# Sheet_Course_Mitr.net
KiCad netlist of a schematic drawn in Altium Designer
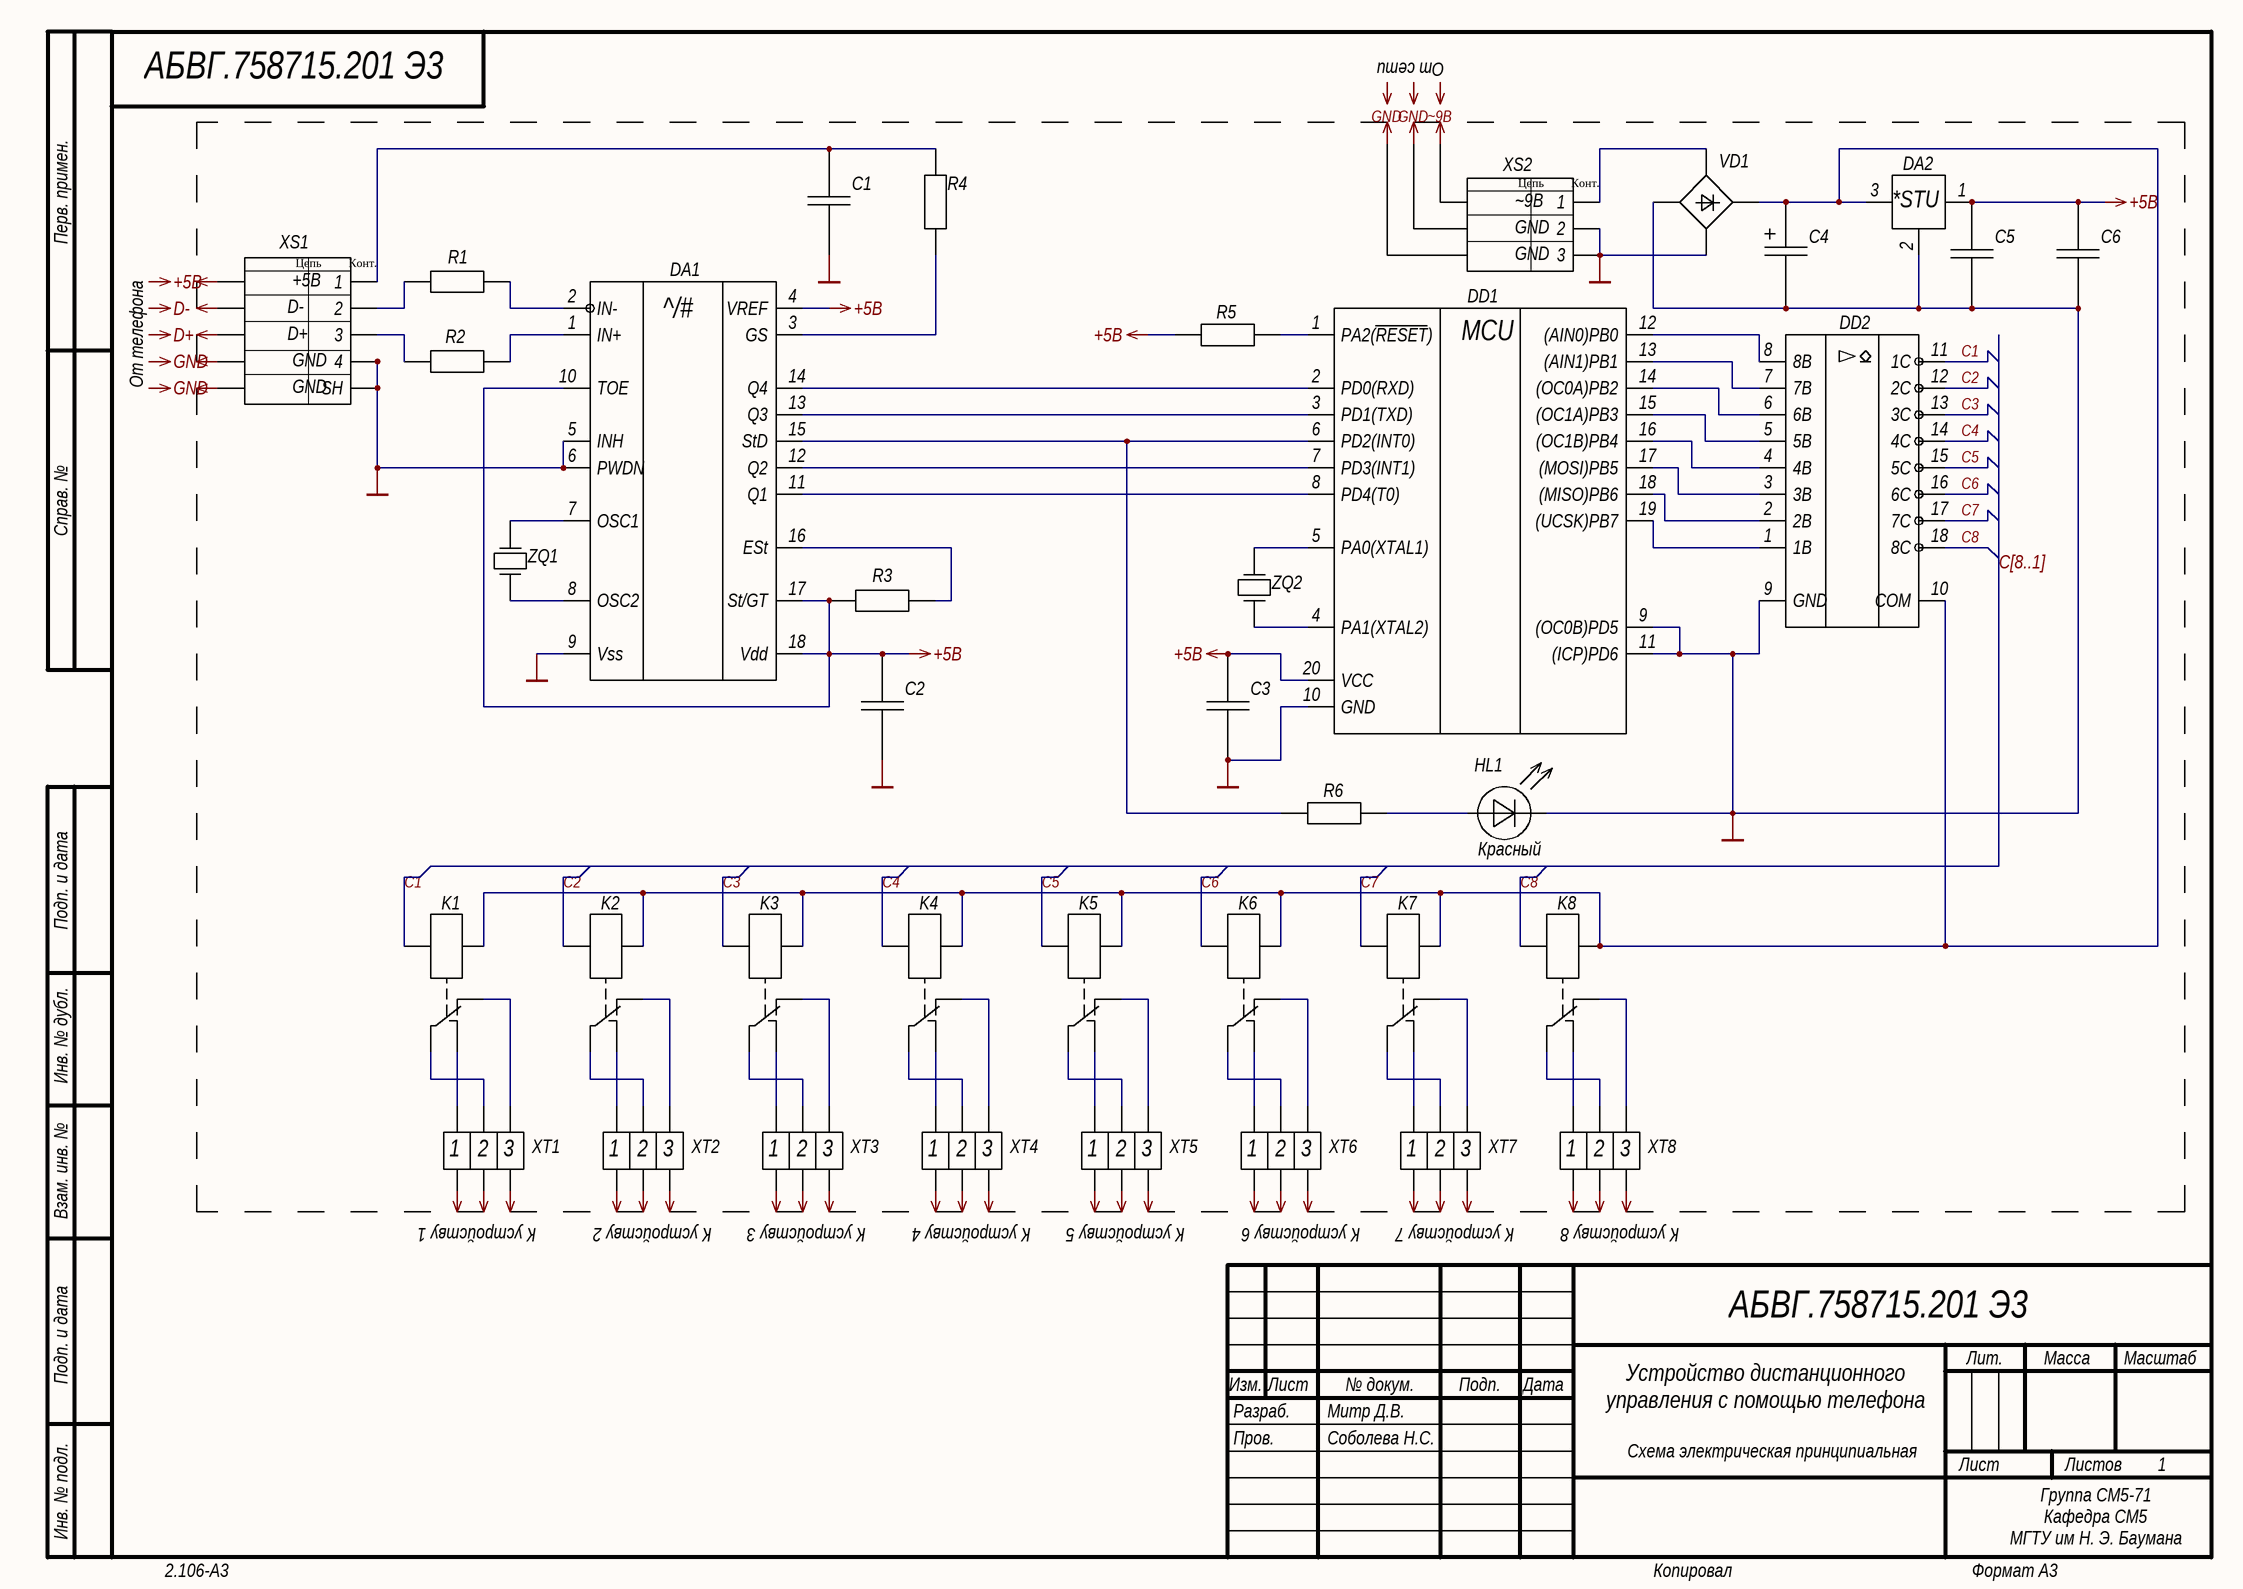
[diagram p0: Sheet_Course_Mitr — копия.SchDoc]

(export (version "E")
  (design (tool "Eeschema 10.0.6"))
  (components
    (comp (ref "C1")
      (value "0,1 мкФ")
      (footprint "0805_CAP")
      (libsource (lib "Schlib_Course_Mitr") (part "Capacitor"))
    )
    (comp (ref "C2")
      (value "0,1 мкФ")
      (footprint "0805_CAP")
      (libsource (lib "Schlib_Course_Mitr") (part "Capacitor"))
    )
    (comp (ref "C3")
      (value "0,1 мкФ")
      (footprint "0805_CAP")
      (libsource (lib "Schlib_Course_Mitr") (part "Capacitor"))
    )
    (comp (ref "C4")
      (value "2200 мкФ")
      (footprint "Pol_CAP")
      (libsource (lib "Schlib_Course_Mitr") (part "Capacitor_pol"))
    )
    (comp (ref "C5")
      (value "0,1 мкФ")
      (footprint "0805_CAP")
      (libsource (lib "Schlib_Course_Mitr") (part "Capacitor"))
    )
    (comp (ref "C6")
      (value "0,1 мкФ")
      (footprint "0805_CAP")
      (libsource (lib "Schlib_Course_Mitr") (part "Capacitor"))
    )
    (comp (ref "DA1")
      (value "MT8870DS")
      (footprint "CM8870C-SOP18")
      (libsource (lib "Schlib_Course_Mitr") (part "MT8870DS"))
    )
    (comp (ref "DA2") (value "78L05") (footprint "STU") (libsource (lib "Schlib_Course_Mitr") (part "STU")))
    (comp (ref "DD1")
      (value "ATtiny2313")
      (footprint "ATtiny2313-SOP20")
      (libsource (lib "Schlib_Course_Mitr") (part "ATtiny2313"))
    )
    (comp (ref "DD2")
      (value "ULN2803A")
      (footprint "ULN2803-SOP18")
      (libsource (lib "Schlib_Course_Mitr") (part "ULN2803A"))
    )
    (comp (ref "HL1")
      (value "Красный")
      (footprint "Blink_RED")
      (fields (field (name "VALUEMANUFACTURERPARTNUMBER") "fyls-0603urc"))
      (libsource (lib "Schlib_Course_Mitr") (part "Led_red"))
    )
    (comp (ref "K1")
      (value "LEG-12")
      (footprint "LEG-12")
      (libsource (lib "Schlib_Course_Mitr") (part "Relay"))
    )
    (comp (ref "K2")
      (value "LEG-12")
      (footprint "LEG-12")
      (libsource (lib "Schlib_Course_Mitr") (part "Relay"))
    )
    (comp (ref "K3")
      (value "LEG-12")
      (footprint "LEG-12")
      (libsource (lib "Schlib_Course_Mitr") (part "Relay"))
    )
    (comp (ref "K4")
      (value "LEG-12")
      (footprint "LEG-12")
      (libsource (lib "Schlib_Course_Mitr") (part "Relay"))
    )
    (comp (ref "K5")
      (value "LEG-12")
      (footprint "LEG-12")
      (libsource (lib "Schlib_Course_Mitr") (part "Relay"))
    )
    (comp (ref "K6")
      (value "LEG-12")
      (footprint "LEG-12")
      (libsource (lib "Schlib_Course_Mitr") (part "Relay"))
    )
    (comp (ref "K7")
      (value "LEG-12")
      (footprint "LEG-12")
      (libsource (lib "Schlib_Course_Mitr") (part "Relay"))
    )
    (comp (ref "K8")
      (value "LEG-12")
      (footprint "LEG-12")
      (libsource (lib "Schlib_Course_Mitr") (part "Relay"))
    )
    (comp (ref "R1")
      (value "100 кОм")
      (footprint "0805_RES")
      (libsource (lib "Schlib_Course_Mitr") (part "Resistor"))
    )
    (comp (ref "R2")
      (value "100 кОм")
      (footprint "0805_RES")
      (libsource (lib "Schlib_Course_Mitr") (part "Resistor"))
    )
    (comp (ref "R3")
      (value "300 кОм")
      (footprint "0805_RES")
      (libsource (lib "Schlib_Course_Mitr") (part "Resistor"))
    )
    (comp (ref "R4")
      (value "100 кОм")
      (footprint "0805_RES")
      (libsource (lib "Schlib_Course_Mitr") (part "Resistor"))
    )
    (comp (ref "R5")
      (value "10 кОм")
      (footprint "0805_RES")
      (libsource (lib "Schlib_Course_Mitr") (part "Resistor"))
    )
    (comp (ref "R6")
      (value "1 кОм")
      (footprint "0805_RES")
      (libsource (lib "Schlib_Course_Mitr") (part "Resistor"))
    )
    (comp (ref "VD1")
      (value "DF04S")
      (footprint "Diode_Bridge")
      (libsource (lib "Schlib_Course_Mitr") (part "Diode_bridge"))
    )
    (comp (ref "XS1")
      (value "USB_TypeB")
      (footprint "USB-B TE Connectivity 292304-1")
      (fields (field (name "VALUEMANUFACTURERPARTNUMBER") "292304-1"))
      (libsource (lib "Schlib_Course_Mitr") (part "USB_TypeB"))
    )
    (comp (ref "XS2")
      (value "DJK-02B")
      (footprint "DJK-02B")
      (libsource (lib "Schlib_Course_Mitr") (part "DJK-02B_PWR_CON"))
    )
    (comp (ref "XT1") (value "KLS2") (footprint "pad") (libsource (lib "Schlib_Course_Mitr") (part "pad")))
    (comp (ref "XT2") (value "KLS2") (footprint "pad") (libsource (lib "Schlib_Course_Mitr") (part "pad")))
    (comp (ref "XT3") (value "KLS2") (footprint "pad") (libsource (lib "Schlib_Course_Mitr") (part "pad")))
    (comp (ref "XT4") (value "KLS2") (footprint "pad") (libsource (lib "Schlib_Course_Mitr") (part "pad")))
    (comp (ref "XT5") (value "KLS2") (footprint "pad") (libsource (lib "Schlib_Course_Mitr") (part "pad")))
    (comp (ref "XT6") (value "KLS2") (footprint "pad") (libsource (lib "Schlib_Course_Mitr") (part "pad")))
    (comp (ref "XT7") (value "KLS2") (footprint "pad") (libsource (lib "Schlib_Course_Mitr") (part "pad")))
    (comp (ref "XT8") (value "KLS2") (footprint "pad") (libsource (lib "Schlib_Course_Mitr") (part "pad")))
    (comp (ref "ZQ1") (value "~") (footprint "Quartz") (libsource (lib "Schlib_Course_Mitr") (part "Quartz")))
    (comp (ref "ZQ2") (value "~") (footprint "Quartz") (libsource (lib "Schlib_Course_Mitr") (part "Quartz")))
  )
  (nets
    (net (code "1") (name "+5В") (class "Default")
      (node (ref "C2") (pin "2") (pinfunction "2_2") (pintype "passive"))
      (node (ref "C3") (pin "2") (pinfunction "2_2") (pintype "passive"))
      (node (ref "C5") (pin "2") (pinfunction "2_2") (pintype "passive"))
      (node (ref "C6") (pin "2") (pinfunction "2_2") (pintype "passive"))
      (node (ref "DA1") (pin "10") (pinfunction "TOE_10") (pintype "passive"))
      (node (ref "DA1") (pin "17") (pinfunction "St/GT_17") (pintype "passive"))
      (node (ref "DA1") (pin "18") (pinfunction "Vdd_18") (pintype "passive"))
      (node (ref "DA1") (pin "4") (pinfunction "VREF_4") (pintype "passive"))
      (node (ref "DA2") (pin "1") (pinfunction "1_1") (pintype "passive"))
      (node (ref "DD1") (pin "20") (pinfunction "VCC_20") (pintype "passive"))
      (node (ref "R3") (pin "1") (pinfunction "1_1") (pintype "passive"))
      (node (ref "R5") (pin "2") (pinfunction "2_2") (pintype "passive"))
    )
    (net (code "2") (name "/C1") (class "Default")
      (node (ref "DD2") (pin "11") (pinfunction "1С_11") (pintype "passive"))
      (node (ref "K1") (pin "5") (pinfunction "5_5") (pintype "passive"))
    )
    (net (code "3") (name "/C8") (class "Default")
      (node (ref "C4") (pin "1") (pinfunction "1_1") (pintype "passive"))
      (node (ref "DA2") (pin "3") (pinfunction "3_3") (pintype "passive"))
      (node (ref "DD2") (pin "10") (pinfunction "COM_10") (pintype "passive"))
      (node (ref "DD2") (pin "12") (pinfunction "2С_12") (pintype "passive"))
      (node (ref "DD2") (pin "13") (pinfunction "3С_13") (pintype "passive"))
      (node (ref "DD2") (pin "14") (pinfunction "4C_14") (pintype "passive"))
      (node (ref "DD2") (pin "15") (pinfunction "5С_15") (pintype "passive"))
      (node (ref "DD2") (pin "16") (pinfunction "6С_16") (pintype "passive"))
      (node (ref "DD2") (pin "17") (pinfunction "7С_17") (pintype "passive"))
      (node (ref "DD2") (pin "18") (pinfunction "8С_18") (pintype "passive"))
      (node (ref "K1") (pin "4") (pinfunction "4_4") (pintype "passive"))
      (node (ref "K2") (pin "4") (pinfunction "4_4") (pintype "passive"))
      (node (ref "K2") (pin "5") (pinfunction "5_5") (pintype "passive"))
      (node (ref "K3") (pin "4") (pinfunction "4_4") (pintype "passive"))
      (node (ref "K3") (pin "5") (pinfunction "5_5") (pintype "passive"))
      (node (ref "K4") (pin "4") (pinfunction "4_4") (pintype "passive"))
      (node (ref "K4") (pin "5") (pinfunction "5_5") (pintype "passive"))
      (node (ref "K5") (pin "4") (pinfunction "4_4") (pintype "passive"))
      (node (ref "K5") (pin "5") (pinfunction "5_5") (pintype "passive"))
      (node (ref "K6") (pin "4") (pinfunction "4_4") (pintype "passive"))
      (node (ref "K6") (pin "5") (pinfunction "5_5") (pintype "passive"))
      (node (ref "K7") (pin "4") (pinfunction "4_4") (pintype "passive"))
      (node (ref "K7") (pin "5") (pinfunction "5_5") (pintype "passive"))
      (node (ref "K8") (pin "4") (pinfunction "4_4") (pintype "passive"))
      (node (ref "K8") (pin "5") (pinfunction "5_5") (pintype "passive"))
      (node (ref "VD1") (pin "2") (pinfunction "2_2") (pintype "passive"))
    )
    (net (code "8") (name "GND") (class "Default")
      (node (ref "C1") (pin "1") (pinfunction "1_1") (pintype "passive"))
      (node (ref "C2") (pin "1") (pinfunction "1_1") (pintype "passive"))
      (node (ref "C3") (pin "1") (pinfunction "1_1") (pintype "passive"))
      (node (ref "C4") (pin "2") (pinfunction "2_2") (pintype "passive"))
      (node (ref "C5") (pin "1") (pinfunction "1_1") (pintype "passive"))
      (node (ref "C6") (pin "1") (pinfunction "1_1") (pintype "passive"))
      (node (ref "DA1") (pin "5") (pinfunction "INH_5") (pintype "passive"))
      (node (ref "DA1") (pin "6") (pinfunction "PWDN_6") (pintype "passive"))
      (node (ref "DA1") (pin "9") (pinfunction "Vss_9") (pintype "passive"))
      (node (ref "DA2") (pin "2") (pinfunction "2_2") (pintype "passive"))
      (node (ref "DD1") (pin "10") (pinfunction "GND_10") (pintype "passive"))
      (node (ref "DD1") (pin "11") (pinfunction "(ICP)PD6_11") (pintype "passive"))
      (node (ref "DD1") (pin "9") (pinfunction "(OC0B)PD5_9") (pintype "passive"))
      (node (ref "DD2") (pin "9") (pinfunction "GND_9") (pintype "passive"))
      (node (ref "HL1") (pin "K") (pinfunction "10_K") (pintype "passive"))
      (node (ref "VD1") (pin "1") (pinfunction "1_1") (pintype "passive"))
      (node (ref "VD1") (pin "4") (pinfunction "4_4") (pintype "passive"))
      (node (ref "XS1") (pin "0") (pinfunction "SH_0") (pintype "passive"))
      (node (ref "XS1") (pin "4") (pinfunction "4_4") (pintype "passive"))
      (node (ref "XS2") (pin "2") (pinfunction "2_2") (pintype "passive"))
      (node (ref "XS2") (pin "3") (pinfunction "3_3") (pintype "passive"))
    )
    (net (code "9") (name "Net-(C1-Pad2)") (class "Default")
      (node (ref "C1") (pin "2") (pinfunction "2_2") (pintype "passive"))
      (node (ref "R4") (pin "1") (pinfunction "1_1") (pintype "passive"))
      (node (ref "XS1") (pin "1") (pinfunction "1_1") (pintype "passive"))
    )
    (net (code "10") (name "Net-(DA1-ESt)") (class "Default")
      (node (ref "DA1") (pin "16") (pinfunction "ESt_16") (pintype "passive"))
      (node (ref "R3") (pin "2") (pinfunction "2_2") (pintype "passive"))
    )
    (net (code "11") (name "Net-(DA1-GS)") (class "Default")
      (node (ref "DA1") (pin "3") (pinfunction "GS_3") (pintype "passive"))
      (node (ref "R4") (pin "2") (pinfunction "2_2") (pintype "passive"))
    )
    (net (code "12") (name "Net-(DA1-IN+)") (class "Default")
      (node (ref "DA1") (pin "1") (pinfunction "IN+_1") (pintype "passive"))
      (node (ref "R2") (pin "1") (pinfunction "1_1") (pintype "passive"))
    )
    (net (code "13") (name "Net-(DA1-IN-)") (class "Default")
      (node (ref "DA1") (pin "2") (pinfunction "IN-_2") (pintype "passive"))
      (node (ref "R1") (pin "1") (pinfunction "1_1") (pintype "passive"))
    )
    (net (code "14") (name "Net-(DA1-OSC1)") (class "Default")
      (node (ref "DA1") (pin "7") (pinfunction "OSC1_7") (pintype "passive"))
      (node (ref "ZQ1") (pin "2") (pinfunction "2_2") (pintype "passive"))
    )
    (net (code "15") (name "Net-(DA1-OSC2)") (class "Default")
      (node (ref "DA1") (pin "8") (pinfunction "OSC2_8") (pintype "passive"))
      (node (ref "ZQ1") (pin "1") (pinfunction "1_1") (pintype "passive"))
    )
    (net (code "16") (name "Net-(DA1-Q1)") (class "Default")
      (node (ref "DA1") (pin "11") (pinfunction "Q1_11") (pintype "passive"))
      (node (ref "DD1") (pin "8") (pinfunction "PD4(T0)_8") (pintype "passive"))
    )
    (net (code "17") (name "Net-(DA1-Q2)") (class "Default")
      (node (ref "DA1") (pin "12") (pinfunction "Q2_12") (pintype "passive"))
      (node (ref "DD1") (pin "7") (pinfunction "PD3(INT1)_7") (pintype "passive"))
    )
    (net (code "18") (name "Net-(DA1-Q3)") (class "Default")
      (node (ref "DA1") (pin "13") (pinfunction "Q3_13") (pintype "passive"))
      (node (ref "DD1") (pin "3") (pinfunction "PD1(TXD)_3") (pintype "passive"))
    )
    (net (code "19") (name "Net-(DA1-Q4)") (class "Default")
      (node (ref "DA1") (pin "14") (pinfunction "Q4_14") (pintype "passive"))
      (node (ref "DD1") (pin "2") (pinfunction "PD0(RXD)_2") (pintype "passive"))
    )
    (net (code "20") (name "Net-(DA1-StD)") (class "Default")
      (node (ref "DA1") (pin "15") (pinfunction "StD_15") (pintype "passive"))
      (node (ref "DD1") (pin "6") (pinfunction "PD2(INT0)_6") (pintype "passive"))
      (node (ref "R6") (pin "2") (pinfunction "2_2") (pintype "passive"))
    )
    (net (code "21") (name "Net-(DD1-(AIN0)PB0)") (class "Default")
      (node (ref "DD1") (pin "12") (pinfunction "(AIN0)PB0_12") (pintype "passive"))
      (node (ref "DD2") (pin "8") (pinfunction "8В_8") (pintype "passive"))
    )
    (net (code "22") (name "Net-(DD1-(AIN1)PB1)") (class "Default")
      (node (ref "DD1") (pin "13") (pinfunction "(AIN1)PB1_13") (pintype "passive"))
      (node (ref "DD2") (pin "7") (pinfunction "7В_7") (pintype "passive"))
    )
    (net (code "23") (name "Net-(DD1-(MISO)PB6)") (class "Default")
      (node (ref "DD1") (pin "18") (pinfunction "(MISO)PB6_18") (pintype "passive"))
      (node (ref "DD2") (pin "2") (pinfunction "2В_2") (pintype "passive"))
    )
    (net (code "24") (name "Net-(DD1-(MOSI)PB5)") (class "Default")
      (node (ref "DD1") (pin "17") (pinfunction "(MOSI)PB5_17") (pintype "passive"))
      (node (ref "DD2") (pin "3") (pinfunction "3В_3") (pintype "passive"))
    )
    (net (code "25") (name "Net-(DD1-(OC0A)PB2)") (class "Default")
      (node (ref "DD1") (pin "14") (pinfunction "(OC0A)PB2_14") (pintype "passive"))
      (node (ref "DD2") (pin "6") (pinfunction "6В_6") (pintype "passive"))
    )
    (net (code "26") (name "Net-(DD1-(OC1A)PB3)") (class "Default")
      (node (ref "DD1") (pin "15") (pinfunction "(OC1A)PB3_15") (pintype "passive"))
      (node (ref "DD2") (pin "5") (pinfunction "5В_5") (pintype "passive"))
    )
    (net (code "27") (name "Net-(DD1-(OC1B)PB4)") (class "Default")
      (node (ref "DD1") (pin "16") (pinfunction "(OC1B)PB4_16") (pintype "passive"))
      (node (ref "DD2") (pin "4") (pinfunction "4В_4") (pintype "passive"))
    )
    (net (code "28") (name "Net-(DD1-(UCSK)PB7)") (class "Default")
      (node (ref "DD1") (pin "19") (pinfunction "(UCSK)PB7_19") (pintype "passive"))
      (node (ref "DD2") (pin "1") (pinfunction "1В_1") (pintype "passive"))
    )
    (net (code "29") (name "Net-(DD1-PA0(XTAL1))") (class "Default")
      (node (ref "DD1") (pin "5") (pinfunction "PA0(XTAL1)_5") (pintype "passive"))
      (node (ref "ZQ2") (pin "2") (pinfunction "2_2") (pintype "passive"))
    )
    (net (code "30") (name "Net-(DD1-PA1(XTAL2))") (class "Default")
      (node (ref "DD1") (pin "4") (pinfunction "PA1(XTAL2)_4") (pintype "passive"))
      (node (ref "ZQ2") (pin "1") (pinfunction "1_1") (pintype "passive"))
    )
    (net (code "31") (name "Net-(DD1-PA2(~{RESET}))") (class "Default")
      (node (ref "DD1") (pin "1") (pinfunction "PA2(~{RESET})_1") (pintype "passive"))
      (node (ref "R5") (pin "1") (pinfunction "1_1") (pintype "passive"))
    )
    (net (code "32") (name "Net-(HL1-9)") (class "Default")
      (node (ref "HL1") (pin "A") (pinfunction "9_A") (pintype "passive"))
      (node (ref "R6") (pin "1") (pinfunction "1_1") (pintype "passive"))
    )
    (net (code "33") (name "Net-(K1-Pad1)") (class "Default")
      (node (ref "K1") (pin "1") (pinfunction "1_1") (pintype "passive"))
      (node (ref "XT1") (pin "1") (pinfunction "1_1") (pintype "passive"))
    )
    (net (code "34") (name "Net-(K1-Pad2)") (class "Default")
      (node (ref "K1") (pin "2") (pinfunction "2_2") (pintype "passive"))
      (node (ref "XT1") (pin "2") (pinfunction "2_2") (pintype "passive"))
    )
    (net (code "35") (name "Net-(K1-Pad3)") (class "Default")
      (node (ref "K1") (pin "3") (pinfunction "3_3") (pintype "passive"))
      (node (ref "XT1") (pin "3") (pinfunction "3_3") (pintype "passive"))
    )
    (net (code "36") (name "Net-(K2-Pad1)") (class "Default")
      (node (ref "K2") (pin "1") (pinfunction "1_1") (pintype "passive"))
      (node (ref "XT2") (pin "1") (pinfunction "1_1") (pintype "passive"))
    )
    (net (code "37") (name "Net-(K2-Pad2)") (class "Default")
      (node (ref "K2") (pin "2") (pinfunction "2_2") (pintype "passive"))
      (node (ref "XT2") (pin "2") (pinfunction "2_2") (pintype "passive"))
    )
    (net (code "38") (name "Net-(K2-Pad3)") (class "Default")
      (node (ref "K2") (pin "3") (pinfunction "3_3") (pintype "passive"))
      (node (ref "XT2") (pin "3") (pinfunction "3_3") (pintype "passive"))
    )
    (net (code "39") (name "Net-(K3-Pad1)") (class "Default")
      (node (ref "K3") (pin "1") (pinfunction "1_1") (pintype "passive"))
      (node (ref "XT3") (pin "1") (pinfunction "1_1") (pintype "passive"))
    )
    (net (code "40") (name "Net-(K3-Pad2)") (class "Default")
      (node (ref "K3") (pin "2") (pinfunction "2_2") (pintype "passive"))
      (node (ref "XT3") (pin "2") (pinfunction "2_2") (pintype "passive"))
    )
    (net (code "41") (name "Net-(K3-Pad3)") (class "Default")
      (node (ref "K3") (pin "3") (pinfunction "3_3") (pintype "passive"))
      (node (ref "XT3") (pin "3") (pinfunction "3_3") (pintype "passive"))
    )
    (net (code "42") (name "Net-(K4-Pad1)") (class "Default")
      (node (ref "K4") (pin "1") (pinfunction "1_1") (pintype "passive"))
      (node (ref "XT4") (pin "1") (pinfunction "1_1") (pintype "passive"))
    )
    (net (code "43") (name "Net-(K4-Pad2)") (class "Default")
      (node (ref "K4") (pin "2") (pinfunction "2_2") (pintype "passive"))
      (node (ref "XT4") (pin "2") (pinfunction "2_2") (pintype "passive"))
    )
    (net (code "44") (name "Net-(K4-Pad3)") (class "Default")
      (node (ref "K4") (pin "3") (pinfunction "3_3") (pintype "passive"))
      (node (ref "XT4") (pin "3") (pinfunction "3_3") (pintype "passive"))
    )
    (net (code "45") (name "Net-(K5-Pad1)") (class "Default")
      (node (ref "K5") (pin "1") (pinfunction "1_1") (pintype "passive"))
      (node (ref "XT5") (pin "1") (pinfunction "1_1") (pintype "passive"))
    )
    (net (code "46") (name "Net-(K5-Pad2)") (class "Default")
      (node (ref "K5") (pin "2") (pinfunction "2_2") (pintype "passive"))
      (node (ref "XT5") (pin "2") (pinfunction "2_2") (pintype "passive"))
    )
    (net (code "47") (name "Net-(K5-Pad3)") (class "Default")
      (node (ref "K5") (pin "3") (pinfunction "3_3") (pintype "passive"))
      (node (ref "XT5") (pin "3") (pinfunction "3_3") (pintype "passive"))
    )
    (net (code "48") (name "Net-(K6-Pad1)") (class "Default")
      (node (ref "K6") (pin "1") (pinfunction "1_1") (pintype "passive"))
      (node (ref "XT6") (pin "1") (pinfunction "1_1") (pintype "passive"))
    )
    (net (code "49") (name "Net-(K6-Pad2)") (class "Default")
      (node (ref "K6") (pin "2") (pinfunction "2_2") (pintype "passive"))
      (node (ref "XT6") (pin "2") (pinfunction "2_2") (pintype "passive"))
    )
    (net (code "50") (name "Net-(K6-Pad3)") (class "Default")
      (node (ref "K6") (pin "3") (pinfunction "3_3") (pintype "passive"))
      (node (ref "XT6") (pin "3") (pinfunction "3_3") (pintype "passive"))
    )
    (net (code "51") (name "Net-(K7-Pad1)") (class "Default")
      (node (ref "K7") (pin "1") (pinfunction "1_1") (pintype "passive"))
      (node (ref "XT7") (pin "1") (pinfunction "1_1") (pintype "passive"))
    )
    (net (code "52") (name "Net-(K7-Pad2)") (class "Default")
      (node (ref "K7") (pin "2") (pinfunction "2_2") (pintype "passive"))
      (node (ref "XT7") (pin "2") (pinfunction "2_2") (pintype "passive"))
    )
    (net (code "53") (name "Net-(K7-Pad3)") (class "Default")
      (node (ref "K7") (pin "3") (pinfunction "3_3") (pintype "passive"))
      (node (ref "XT7") (pin "3") (pinfunction "3_3") (pintype "passive"))
    )
    (net (code "54") (name "Net-(K8-Pad1)") (class "Default")
      (node (ref "K8") (pin "1") (pinfunction "1_1") (pintype "passive"))
      (node (ref "XT8") (pin "1") (pinfunction "1_1") (pintype "passive"))
    )
    (net (code "55") (name "Net-(K8-Pad2)") (class "Default")
      (node (ref "K8") (pin "2") (pinfunction "2_2") (pintype "passive"))
      (node (ref "XT8") (pin "2") (pinfunction "2_2") (pintype "passive"))
    )
    (net (code "56") (name "Net-(K8-Pad3)") (class "Default")
      (node (ref "K8") (pin "3") (pinfunction "3_3") (pintype "passive"))
      (node (ref "XT8") (pin "3") (pinfunction "3_3") (pintype "passive"))
    )
    (net (code "57") (name "Net-(R1-Pad2)") (class "Default")
      (node (ref "R1") (pin "2") (pinfunction "2_2") (pintype "passive"))
      (node (ref "XS1") (pin "2") (pinfunction "2_2") (pintype "passive"))
    )
    (net (code "58") (name "Net-(R2-Pad2)") (class "Default")
      (node (ref "R2") (pin "2") (pinfunction "2_2") (pintype "passive"))
      (node (ref "XS1") (pin "3") (pinfunction "3_3") (pintype "passive"))
    )
    (net (code "59") (name "Net-(VD1-Pad3)") (class "Default")
      (node (ref "VD1") (pin "3") (pinfunction "3_3") (pintype "passive"))
      (node (ref "XS2") (pin "1") (pinfunction "1_1") (pintype "passive"))
    )
  )
)
